# IoT_Greenhouse_V1_0_A_-_Inputs.net
KiCad netlist of a schematic drawn in Altium Designer
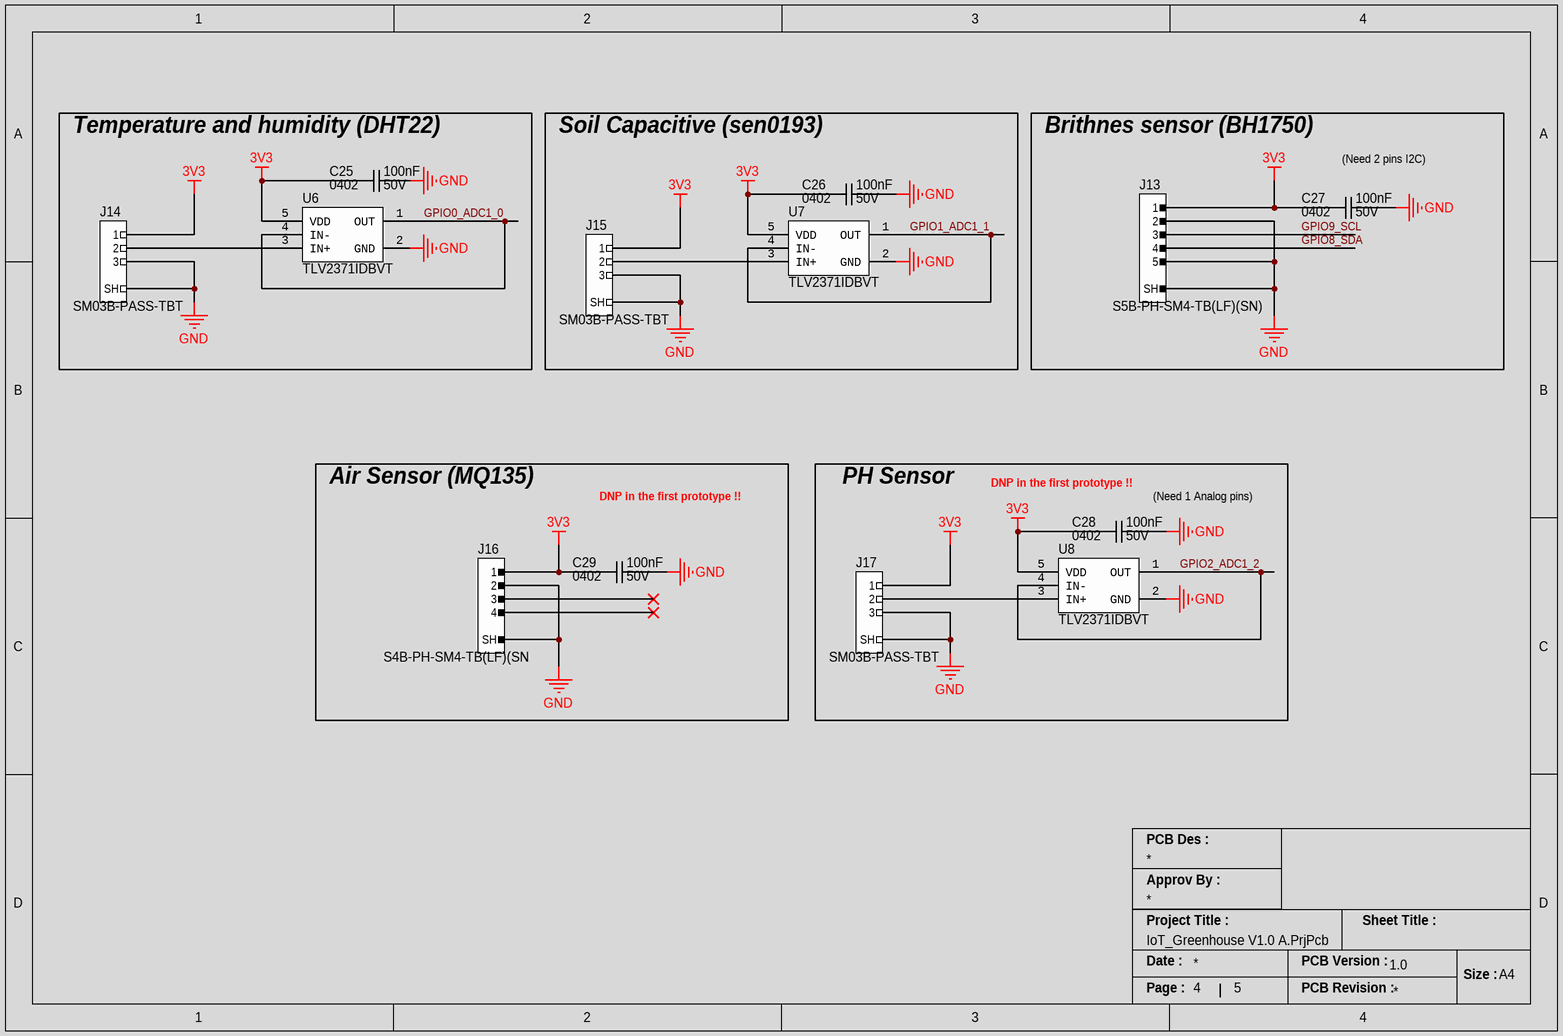
[diagram p0: IoT_Greenhouse V1.0 A - Inputs.SchDoc]

(export (version "E")
  (design (tool "Eeschema 10.0.6"))
  (components
    (comp (ref "C25")
      (value "GRM155R71H104KE14D")
      (footprint "CAP_0402_CAPC1005X05N")
      (description "Multilayer Ceramic Capacitor, 0.1 uF, 16 V, ± 10%, X7R, 0402 [1005 Metric]")
      (fields
        (field (name "MANUFACTURER") "Murata")
        (field (name "TOLERANCE") "10%")
        (field (name "VOLTAGE RATING") "50V")
        (field (name "CAPACITANCE") "100nF")
        (field (name "CASE/PACKAGE") "0402")
      )
      (libsource (lib "Electronic Devices_LIB") (part "CAP_100NF_50V_X7R_0402"))
    )
    (comp (ref "C26")
      (value "GRM155R71H104KE14D")
      (footprint "CAP_0402_CAPC1005X05N")
      (description "Multilayer Ceramic Capacitor, 0.1 uF, 16 V, ± 10%, X7R, 0402 [1005 Metric]")
      (fields
        (field (name "MANUFACTURER") "Murata")
        (field (name "TOLERANCE") "10%")
        (field (name "VOLTAGE RATING") "50V")
        (field (name "CAPACITANCE") "100nF")
        (field (name "CASE/PACKAGE") "0402")
      )
      (libsource (lib "Electronic Devices_LIB") (part "CAP_100NF_50V_X7R_0402"))
    )
    (comp (ref "C27")
      (value "GRM155R71H104KE14D")
      (footprint "CAP_0402_CAPC1005X05N")
      (description "Multilayer Ceramic Capacitor, 0.1 uF, 16 V, ± 10%, X7R, 0402 [1005 Metric]")
      (fields
        (field (name "MANUFACTURER") "Murata")
        (field (name "TOLERANCE") "10%")
        (field (name "VOLTAGE RATING") "50V")
        (field (name "CAPACITANCE") "100nF")
        (field (name "CASE/PACKAGE") "0402")
      )
      (libsource (lib "Electronic Devices_LIB") (part "CAP_100NF_50V_X7R_0402"))
    )
    (comp (ref "C28")
      (value "GRM155R71H104KE14D")
      (footprint "CAP_0402_CAPC1005X05N")
      (description "Multilayer Ceramic Capacitor, 0.1 uF, 16 V, ± 10%, X7R, 0402 [1005 Metric]")
      (fields
        (field (name "MANUFACTURER") "Murata")
        (field (name "TOLERANCE") "10%")
        (field (name "VOLTAGE RATING") "50V")
        (field (name "CAPACITANCE") "100nF")
        (field (name "CASE/PACKAGE") "0402")
      )
      (libsource (lib "Electronic Devices_LIB") (part "CAP_100NF_50V_X7R_0402"))
    )
    (comp (ref "C29")
      (value "GRM155R71H104KE14D")
      (footprint "CAP_0402_CAPC1005X05N")
      (description "Multilayer Ceramic Capacitor, 0.1 uF, 16 V, ± 10%, X7R, 0402 [1005 Metric]")
      (fields
        (field (name "MANUFACTURER") "Murata")
        (field (name "TOLERANCE") "10%")
        (field (name "VOLTAGE RATING") "50V")
        (field (name "CAPACITANCE") "100nF")
        (field (name "CASE/PACKAGE") "0402")
      )
      (libsource (lib "Electronic Devices_LIB") (part "CAP_100NF_50V_X7R_0402"))
    )
    (comp (ref "J13")
      (value "S5B-PH-SM4-TB(LF)(SN)")
      (footprint "CONN_JST_S5B-PH-SM4-TB_LF_SN_0")
      (description "Conn Shrouded Header (4 Sides) HDR 5 POS 2mm Solder RA SMD T/R")
      (fields (field (name "MANUFACTURER") "JST"))
      (libsource (lib "Electronic Devices_LIB") (part "CONN_JST_PH_RA_5P_2mm"))
    )
    (comp (ref "J14")
      (value "SM03B-PASS-TBT")
      (footprint "CONN_JST_SM03B-PASS-TBT_LF_SN_MFG")
      (description "Conn Header SMD R/a 3POS 2MM")
      (fields (field (name "MANUFACTURER") "JST"))
      (libsource (lib "Electronic Devices_LIB") (part "CONN_JST_PH_3P_2MM_SM03B-PASS-TBT"))
    )
    (comp (ref "J15")
      (value "SM03B-PASS-TBT")
      (footprint "CONN_JST_SM03B-PASS-TBT_LF_SN_MFG")
      (description "Conn Header SMD R/a 3POS 2MM")
      (fields (field (name "MANUFACTURER") "JST"))
      (libsource (lib "Electronic Devices_LIB") (part "CONN_JST_PH_3P_2MM_SM03B-PASS-TBT"))
    )
    (comp (ref "J16")
      (value "S4B-PH-SM4-TB(LF)(SN")
      (footprint "CONN_JST_S4B-PH-SM4-TB_LF_SN_0")
      (fields (field (name "MANUFACTURER") "JST") (field (name "JLCPCB PART NUMBER") "C265102"))
      (libsource (lib "Electronic Devices_LIB") (part "CONN_JST_PH_RA_4P_2mm_JLCPCB"))
    )
    (comp (ref "J17")
      (value "SM03B-PASS-TBT")
      (footprint "CONN_JST_SM03B-PASS-TBT_LF_SN_MFG")
      (description "Conn Header SMD R/a 3POS 2MM")
      (fields (field (name "MANUFACTURER") "JST"))
      (libsource (lib "Electronic Devices_LIB") (part "CONN_JST_PH_3P_2MM_SM03B-PASS-TBT"))
    )
    (comp (ref "U6")
      (value "TLV2371IDBVT")
      (footprint "IC_AMP_OP_SOT95P280X145-5N")
      (description "Single 550-uA/channel, 3MHz, RRIO op amp 5-SOT-23 -40 to 125")
      (fields (field (name "MANUFACTURER") "Texas Instruments"))
      (libsource (lib "Electronic Devices_LIB") (part "IC_AMP_OP_TLV2371IDBVT"))
    )
    (comp (ref "U7")
      (value "TLV2371IDBVT")
      (footprint "IC_AMP_OP_SOT95P280X145-5N")
      (description "Single 550-uA/channel, 3MHz, RRIO op amp 5-SOT-23 -40 to 125")
      (fields (field (name "MANUFACTURER") "Texas Instruments"))
      (libsource (lib "Electronic Devices_LIB") (part "IC_AMP_OP_TLV2371IDBVT"))
    )
    (comp (ref "U8")
      (value "TLV2371IDBVT")
      (footprint "IC_AMP_OP_SOT95P280X145-5N")
      (description "Single 550-uA/channel, 3MHz, RRIO op amp 5-SOT-23 -40 to 125")
      (fields (field (name "MANUFACTURER") "Texas Instruments"))
      (libsource (lib "Electronic Devices_LIB") (part "IC_AMP_OP_TLV2371IDBVT"))
    )
  )
  (nets
    (net (code "1") (name "/GPIO0_ADC1_0") (class "Default")
      (node (ref "U6") (pin "1") (pinfunction "OUT_1") (pintype "passive"))
      (node (ref "U6") (pin "4") (pinfunction "IN-_4") (pintype "passive"))
    )
    (net (code "2") (name "/GPIO1_ADC1_1") (class "Default")
      (node (ref "U7") (pin "1") (pinfunction "OUT_1") (pintype "passive"))
      (node (ref "U7") (pin "4") (pinfunction "IN-_4") (pintype "passive"))
    )
    (net (code "3") (name "/GPIO2_ADC1_2") (class "Default")
      (node (ref "U8") (pin "1") (pinfunction "OUT_1") (pintype "passive"))
      (node (ref "U8") (pin "4") (pinfunction "IN-_4") (pintype "passive"))
    )
    (net (code "4") (name "/GPIO8_SDA") (class "Default")
      (node (ref "J13") (pin "4") (pinfunction "4_4") (pintype "passive"))
    )
    (net (code "5") (name "/GPIO9_SCL") (class "Default")
      (node (ref "J13") (pin "3") (pinfunction "3_3") (pintype "passive"))
    )
    (net (code "6") (name "3V3") (class "Default")
      (node (ref "C25") (pin "2") (pinfunction "2_2") (pintype "passive"))
      (node (ref "C26") (pin "2") (pinfunction "2_2") (pintype "passive"))
      (node (ref "C27") (pin "2") (pinfunction "2_2") (pintype "passive"))
      (node (ref "C28") (pin "2") (pinfunction "2_2") (pintype "passive"))
      (node (ref "C29") (pin "2") (pinfunction "2_2") (pintype "passive"))
      (node (ref "J13") (pin "1") (pinfunction "1_1") (pintype "passive"))
      (node (ref "J14") (pin "1") (pinfunction "1_1") (pintype "passive"))
      (node (ref "J15") (pin "1") (pinfunction "1_1") (pintype "passive"))
      (node (ref "J16") (pin "1") (pinfunction "1_1") (pintype "passive"))
      (node (ref "J17") (pin "1") (pinfunction "1_1") (pintype "passive"))
      (node (ref "U6") (pin "5") (pinfunction "VDD_5") (pintype "power_in"))
      (node (ref "U7") (pin "5") (pinfunction "VDD_5") (pintype "power_in"))
      (node (ref "U8") (pin "5") (pinfunction "VDD_5") (pintype "power_in"))
    )
    (net (code "7") (name "GND") (class "Default")
      (node (ref "C25") (pin "1") (pinfunction "1_1") (pintype "passive"))
      (node (ref "C26") (pin "1") (pinfunction "1_1") (pintype "passive"))
      (node (ref "C27") (pin "1") (pinfunction "1_1") (pintype "passive"))
      (node (ref "C28") (pin "1") (pinfunction "1_1") (pintype "passive"))
      (node (ref "C29") (pin "1") (pinfunction "1_1") (pintype "passive"))
      (node (ref "J13") (pin "0") (pinfunction "SH_0") (pintype "passive"))
      (node (ref "J13") (pin "2") (pinfunction "2_2") (pintype "passive"))
      (node (ref "J13") (pin "5") (pinfunction "5_5") (pintype "passive"))
      (node (ref "J14") (pin "3") (pinfunction "3_3") (pintype "passive"))
      (node (ref "J14") (pin "SH") (pinfunction "SH_SH") (pintype "passive"))
      (node (ref "J15") (pin "3") (pinfunction "3_3") (pintype "passive"))
      (node (ref "J15") (pin "SH") (pinfunction "SH_SH") (pintype "passive"))
      (node (ref "J16") (pin "0") (pinfunction "SH_0") (pintype "passive"))
      (node (ref "J16") (pin "2") (pinfunction "2_2") (pintype "passive"))
      (node (ref "J17") (pin "3") (pinfunction "3_3") (pintype "passive"))
      (node (ref "J17") (pin "SH") (pinfunction "SH_SH") (pintype "passive"))
      (node (ref "U6") (pin "2") (pinfunction "GND_2") (pintype "power_in"))
      (node (ref "U7") (pin "2") (pinfunction "GND_2") (pintype "power_in"))
      (node (ref "U8") (pin "2") (pinfunction "GND_2") (pintype "power_in"))
    )
    (net (code "8") (name "Net-(U6-IN+)") (class "Default")
      (node (ref "J14") (pin "2") (pinfunction "2_2") (pintype "passive"))
      (node (ref "U6") (pin "3") (pinfunction "IN+_3") (pintype "passive"))
    )
    (net (code "9") (name "Net-(U7-IN+)") (class "Default")
      (node (ref "J15") (pin "2") (pinfunction "2_2") (pintype "passive"))
      (node (ref "U7") (pin "3") (pinfunction "IN+_3") (pintype "passive"))
    )
    (net (code "10") (name "Net-(U8-IN+)") (class "Default")
      (node (ref "J17") (pin "2") (pinfunction "2_2") (pintype "passive"))
      (node (ref "U8") (pin "3") (pinfunction "IN+_3") (pintype "passive"))
    )
    (net (code "11") (name "unconnected-(J16-Pad3)") (class "Default")
      (node (ref "J16") (pin "3") (pinfunction "3_3") (pintype "passive+no_connect"))
    )
    (net (code "12") (name "unconnected-(J16-Pad4)") (class "Default")
      (node (ref "J16") (pin "4") (pinfunction "4_4") (pintype "passive+no_connect"))
    )
  )
)
